# ledboard2.net
KiCad netlist of a schematic drawn in EAGLE
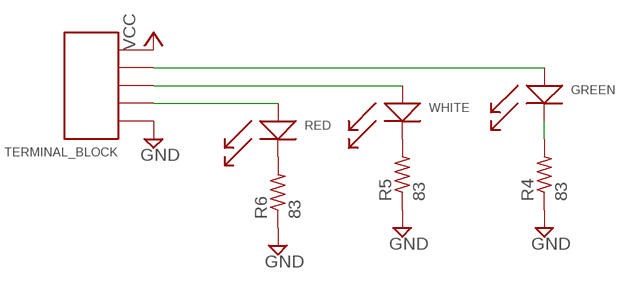
[diagram p0: schematic, sheet 1]

(export (version "E")
  (design (tool "Eeschema 10.0.6"))
  (components
    (comp (ref "GREEN")
      (value "8MM_LED")
      (footprint "eagle-import:8MM_LED")
      (libsource (lib "eagle-import") (part "8MM_LED"))
    )
    (comp (ref "R4")
      (value "83")
      (footprint "eagle-import:0207_12")
      (libsource (lib "eagle-import") (part "R-US_0207/12"))
    )
    (comp (ref "R5")
      (value "83")
      (footprint "eagle-import:0207_12")
      (libsource (lib "eagle-import") (part "R-US_0207/12"))
    )
    (comp (ref "R6")
      (value "83")
      (footprint "eagle-import:0207_12")
      (libsource (lib "eagle-import") (part "R-US_0207/12"))
    )
    (comp (ref "RED")
      (value "8MM_LED")
      (footprint "eagle-import:8MM_LED")
      (libsource (lib "eagle-import") (part "8MM_LED"))
    )
    (comp (ref "TERMINAL_BLOCK")
      (value "1X5_3.5MM_TERMINAL_BLOCK")
      (footprint "eagle-import:1X5_3.5MM_TERMINAL_BLOCK")
      (libsource (lib "eagle-import") (part "1X5_3.5MM_TERMINAL_BLOCK"))
    )
    (comp (ref "WHITE")
      (value "8MM_LED")
      (footprint "eagle-import:8MM_LED")
      (libsource (lib "eagle-import") (part "8MM_LED"))
    )
  )
  (nets
    (net (code "1") (name "GND") (class "Default")
      (node (ref "R4") (pin "1") (pinfunction "1_1") (pintype "passive"))
      (node (ref "R5") (pin "1") (pinfunction "1_1") (pintype "passive"))
      (node (ref "R6") (pin "1") (pinfunction "1_1") (pintype "passive"))
      (node (ref "TERMINAL_BLOCK") (pin "5") (pinfunction "5_5") (pintype "bidirectional"))
    )
    (net (code "2") (name "Net-(GREEN-PadNEG)") (class "Default")
      (node (ref "GREEN") (pin "NEG") (pinfunction "NEG_NEG") (pintype "bidirectional"))
      (node (ref "R4") (pin "2") (pinfunction "2_2") (pintype "passive"))
    )
    (net (code "3") (name "Net-(GREEN-PadPOS)") (class "Default")
      (node (ref "GREEN") (pin "POS") (pinfunction "POS_POS") (pintype "bidirectional"))
      (node (ref "TERMINAL_BLOCK") (pin "2") (pinfunction "2_2") (pintype "bidirectional"))
    )
    (net (code "4") (name "Net-(R5-Pad2)") (class "Default")
      (node (ref "R5") (pin "2") (pinfunction "2_2") (pintype "passive"))
      (node (ref "WHITE") (pin "NEG") (pinfunction "NEG_NEG") (pintype "bidirectional"))
    )
    (net (code "5") (name "Net-(R6-Pad2)") (class "Default")
      (node (ref "R6") (pin "2") (pinfunction "2_2") (pintype "passive"))
      (node (ref "RED") (pin "NEG") (pinfunction "NEG_NEG") (pintype "bidirectional"))
    )
    (net (code "6") (name "Net-(RED-PadPOS)") (class "Default")
      (node (ref "RED") (pin "POS") (pinfunction "POS_POS") (pintype "bidirectional"))
      (node (ref "TERMINAL_BLOCK") (pin "4") (pinfunction "4_4") (pintype "bidirectional"))
    )
    (net (code "7") (name "Net-(TERMINAL_BLOCK-Pad3)") (class "Default")
      (node (ref "TERMINAL_BLOCK") (pin "3") (pinfunction "3_3") (pintype "bidirectional"))
      (node (ref "WHITE") (pin "POS") (pinfunction "POS_POS") (pintype "bidirectional"))
    )
    (net (code "8") (name "VCC") (class "Default")
      (node (ref "TERMINAL_BLOCK") (pin "1") (pinfunction "1_1") (pintype "bidirectional"))
    )
  )
)
